# Microcontroller.net
KiCad netlist of a schematic drawn in Altium Designer
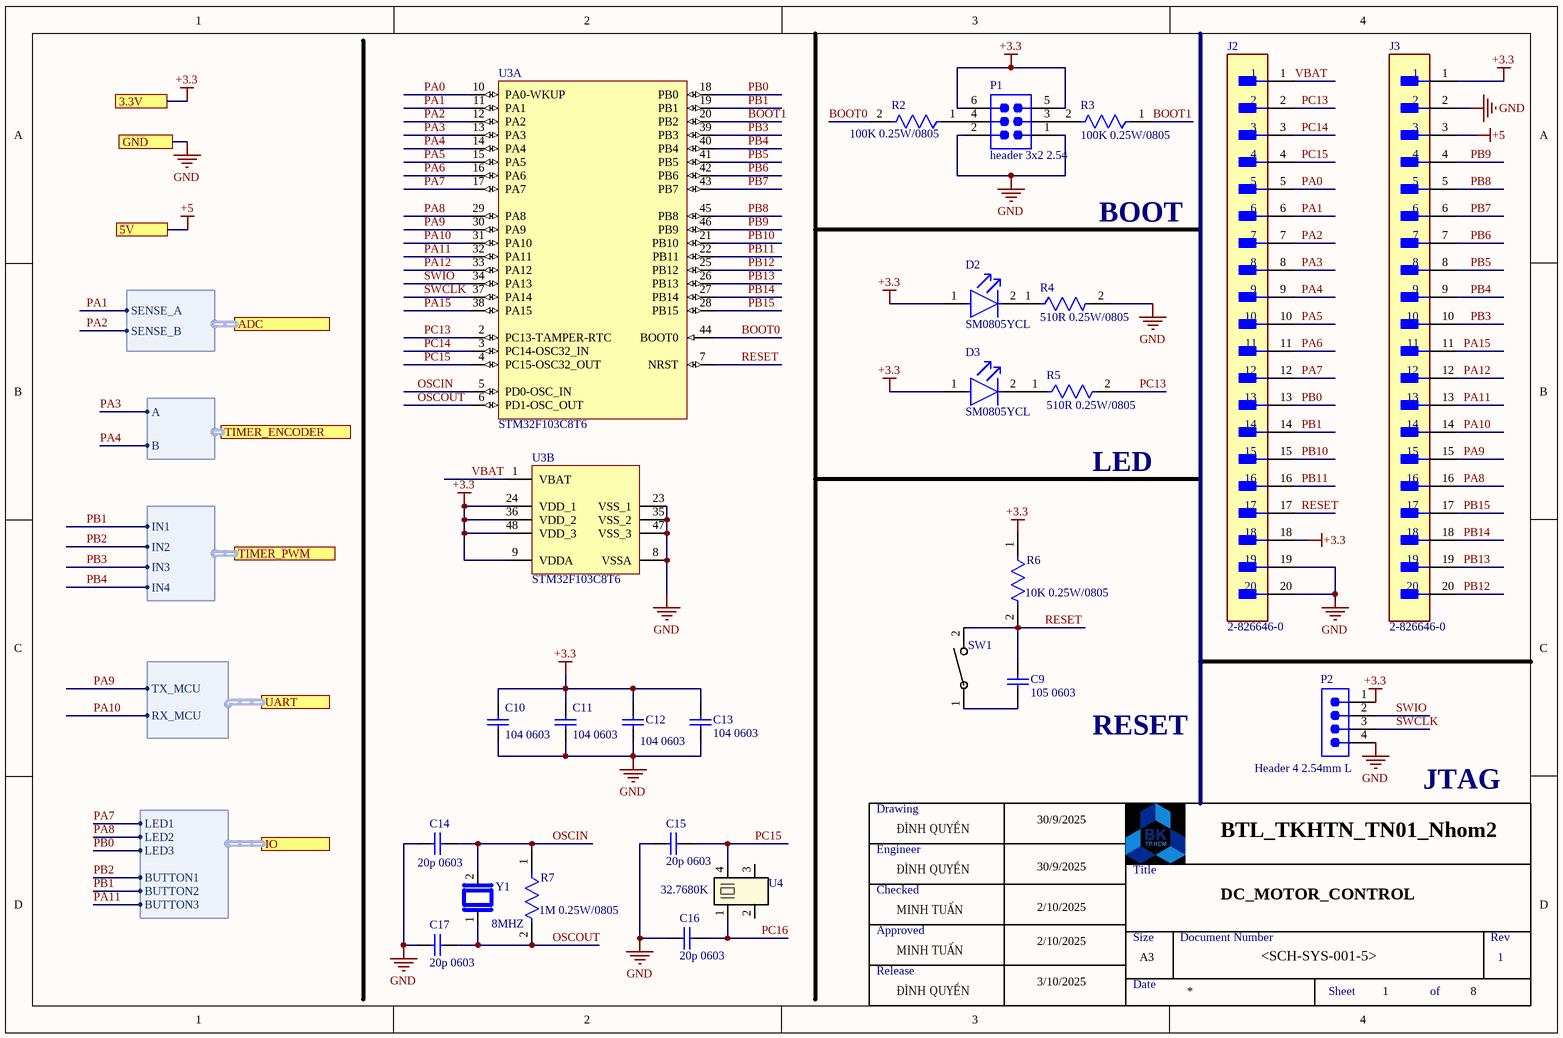
[diagram p0: Microcontroller.SchDoc]

(export (version "E")
  (design (tool "Eeschema 10.0.6"))
  (components
    (comp (ref "C9")
      (value "105 0603")
      (footprint "CAPC1608X92X38ML15T08")
      (fields (field (name "MANUFACTURER") "Vitramon") (field (name "PART NUMBER") "VJ0603Y103JXXAC"))
      (libsource (lib "Altium Content Vault") (part "CAP"))
    )
    (comp (ref "C10")
      (value "104 0603")
      (footprint "CAPC1608X92X38ML15T08")
      (fields (field (name "MANUFACTURER") "Vitramon") (field (name "PART NUMBER") "VJ0603Y103JXXAC"))
      (libsource (lib "Altium Content Vault") (part "CAP"))
    )
    (comp (ref "C11")
      (value "104 0603")
      (footprint "CAPC1608X92X38ML15T08")
      (fields (field (name "MANUFACTURER") "Vitramon") (field (name "PART NUMBER") "VJ0603Y103JXXAC"))
      (libsource (lib "Altium Content Vault") (part "CAP"))
    )
    (comp (ref "C12")
      (value "104 0603")
      (footprint "CAPC1608X92X38ML15T08")
      (fields (field (name "MANUFACTURER") "Vitramon") (field (name "PART NUMBER") "VJ0603Y103JXXAC"))
      (libsource (lib "Altium Content Vault") (part "CAP"))
    )
    (comp (ref "C13")
      (value "104 0603")
      (footprint "CAPC1608X92X38ML15T08")
      (fields (field (name "MANUFACTURER") "Vitramon") (field (name "PART NUMBER") "VJ0603Y103JXXAC"))
      (libsource (lib "Altium Content Vault") (part "CAP"))
    )
    (comp (ref "C14")
      (value "20p 0603")
      (footprint "CAPC1608X92X38ML15T08")
      (fields (field (name "MANUFACTURER") "Vitramon") (field (name "PART NUMBER") "VJ0603Y103JXXAC"))
      (libsource (lib "Altium Content Vault") (part "CAP"))
    )
    (comp (ref "C15")
      (value "20p 0603")
      (footprint "CAPC1608X92X38ML15T08")
      (fields (field (name "MANUFACTURER") "Vitramon") (field (name "PART NUMBER") "VJ0603Y103JXXAC"))
      (libsource (lib "Altium Content Vault") (part "CAP"))
    )
    (comp (ref "C16")
      (value "20p 0603")
      (footprint "CAPC1608X92X38ML15T08")
      (fields (field (name "MANUFACTURER") "Vitramon") (field (name "PART NUMBER") "VJ0603Y103JXXAC"))
      (libsource (lib "Altium Content Vault") (part "CAP"))
    )
    (comp (ref "C17")
      (value "20p 0603")
      (footprint "CAPC1608X92X38ML15T08")
      (fields (field (name "MANUFACTURER") "Vitramon") (field (name "PART NUMBER") "VJ0603Y103JXXAC"))
      (libsource (lib "Altium Content Vault") (part "CAP"))
    )
    (comp (ref "D2")
      (value "SM0805YCL")
      (footprint "FP-SM0805YCL-MFG")
      (description "LED YELLOW CLEAR 0805 SMD")
      (libsource (lib "Altium Content Vault") (part "ab1c01a81903e929fc6c44469aada92"))
    )
    (comp (ref "D3")
      (value "SM0805YCL")
      (footprint "FP-SM0805YCL-MFG")
      (description "LED YELLOW CLEAR 0805 SMD")
      (libsource (lib "Altium Content Vault") (part "ab1c01a81903e929fc6c44469aada92"))
    )
    (comp (ref "J2")
      (value "2-826646-0")
      (footprint "FP-2-826646-0-MFG")
      (description "CONN HEADER VERT 20POS 2.54MM")
      (libsource (lib "Altium Content Vault") (part "09d5f2461bb0697fba3bd732061644e"))
    )
    (comp (ref "J3")
      (value "2-826646-0")
      (footprint "FP-2-826646-0-MFG")
      (description "CONN HEADER VERT 20POS 2.54MM")
      (libsource (lib "Altium Content Vault") (part "09d5f2461bb0697fba3bd732061644e"))
    )
    (comp (ref "P1")
      (value "header 3x2 2.54")
      (footprint "SMTC-TSW-103-08-X-D")
      (description "0.025\" SQ Post Header, Through-hole, Vertical, -55 to 125 degC, 2.54 mm Pitch, 6-Pin, Male, RoHS")
      (fields (field (name "MANUFACTURER") "Samtec") (field (name "PARTNUMBER") "TSW-103-08-F-D"))
      (libsource (lib "Altium Content Vault") (part "SMTC-TSW-103-08-X-D"))
    )
    (comp (ref "P2")
      (value "Header 4 2.54mm L")
      (footprint "SMTC-TSW-104-08-X-S")
      (description "0.025\" SQ Post Header, Through-hole, Vertical, -55 to 125 degC, 2.54 mm Pitch, 4-Pin, Male, RoHS")
      (fields (field (name "MANUFACTURER") "Samtec") (field (name "PARTNUMBER") "TSW-104-08-G-S"))
      (libsource (lib "Altium Content Vault") (part "SMTC-TSW-104-08-X-S"))
    )
    (comp (ref "R2")
      (value "100K 0.25W/0805")
      (footprint "FP-AF0805-IPC_C")
      (description "Anti-Sulfurated Chip Resistor Automotive Grade 75Ω 1% 0.125W ±100ppm/°C 0805")
      (fields (field (name "TOLERANCE") "1%"))
      (libsource (lib "Altium Content Vault") (part "1029c3af85768c4190bb7ad29bc67b5"))
    )
    (comp (ref "R3")
      (value "100K 0.25W/0805")
      (footprint "FP-AF0805-IPC_C")
      (description "Anti-Sulfurated Chip Resistor Automotive Grade 75Ω 1% 0.125W ±100ppm/°C 0805")
      (fields (field (name "TOLERANCE") "1%"))
      (libsource (lib "Altium Content Vault") (part "1029c3af85768c4190bb7ad29bc67b5"))
    )
    (comp (ref "R4")
      (value "510R 0.25W/0805")
      (footprint "FP-AF0805-IPC_C")
      (description "Anti-Sulfurated Chip Resistor Automotive Grade 75Ω 1% 0.125W ±100ppm/°C 0805")
      (fields (field (name "TOLERANCE") "1%"))
      (libsource (lib "Altium Content Vault") (part "1029c3af85768c4190bb7ad29bc67b5"))
    )
    (comp (ref "R5")
      (value "510R 0.25W/0805")
      (footprint "FP-AF0805-IPC_C")
      (description "Anti-Sulfurated Chip Resistor Automotive Grade 75Ω 1% 0.125W ±100ppm/°C 0805")
      (fields (field (name "TOLERANCE") "1%"))
      (libsource (lib "Altium Content Vault") (part "1029c3af85768c4190bb7ad29bc67b5"))
    )
    (comp (ref "R6")
      (value "10K 0.25W/0805")
      (footprint "FP-AF0805-IPC_C")
      (description "Anti-Sulfurated Chip Resistor Automotive Grade 75Ω 1% 0.125W ±100ppm/°C 0805")
      (fields (field (name "TOLERANCE") "1%"))
      (libsource (lib "Altium Content Vault") (part "1029c3af85768c4190bb7ad29bc67b5"))
    )
    (comp (ref "R7")
      (value "1M 0.25W/0805")
      (footprint "FP-AF0805-IPC_C")
      (description "Anti-Sulfurated Chip Resistor Automotive Grade 75Ω 1% 0.125W ±100ppm/°C 0805")
      (fields (field (name "TOLERANCE") "1%"))
      (libsource (lib "Altium Content Vault") (part "1029c3af85768c4190bb7ad29bc67b5"))
    )
    (comp (ref "SW1")
      (value "PTS636 SM50J SMTR LFS")
      (footprint "SW_PTS636_CNK")
      (description "No Description Available")
      (fields (field (name "COPYRIGHT") "Copyright (C) 2025 Ultra Librarian. All rights reserved."))
      (libsource (lib "PTS636SM50JSMTRLFS") (part "PTS636 SM50J SMTR LFS"))
    )
    (comp (ref "U3")
      (value "STM32F103C8T6")
      (footprint "STM-LQFP48_L")
      (libsource (lib "Altium Content Vault") (part "MC-ARM-STM32F103X8_B-SQ48"))
    )
    (comp (ref "U4")
      (value "32.7680K")
      (footprint "SOJ_MC-306_EPS")
      (description "No Description Available")
      (fields
        (field (name "MANUFACTURER_PART_NUMBER") "MC-306 32.7680K-A3: ROHS")
        (field (name "COPYRIGHT") "Copyright (C) 2025 Ultra Librarian. All rights reserved.")
      )
      (libsource (lib "MC-30632P7680K-A3&colon_ROHS") (part "MC-306 32.7680K-A3{colon} ROHS"))
    )
    (comp (ref "Y1")
      (value "8MHZ")
      (footprint "XTAL_HC49P488W43L1150T466H350")
      (description "16 MHz Â±30ppm Crystal 18pF 50 Ohms HC-49/US")
      (fields (field (name "MF") "Citizen Finedevice") (field (name "MP") "HC-49/U-S16000000ABJB"))
      (libsource (lib "HC-49_U-S16000000ABJB") (part "HC-49/U-S16000000ABJB"))
    )
  )
  (nets
    (net (code "6") (name "+3.3") (class "Default")
      (node (ref "C10") (pin "2") (pinfunction "2_2") (pintype "passive"))
      (node (ref "C11") (pin "2") (pinfunction "2_2") (pintype "passive"))
      (node (ref "C12") (pin "2") (pinfunction "2_2") (pintype "passive"))
      (node (ref "C13") (pin "2") (pinfunction "2_2") (pintype "passive"))
      (node (ref "D2") (pin "1") (pinfunction "A_1") (pintype "passive"))
      (node (ref "D3") (pin "1") (pinfunction "A_1") (pintype "passive"))
      (node (ref "J2") (pin "18") (pinfunction "18_18") (pintype "passive"))
      (node (ref "J3") (pin "1") (pinfunction "1_1") (pintype "passive"))
      (node (ref "P1") (pin "5") (pinfunction "5_5") (pintype "passive"))
      (node (ref "P1") (pin "6") (pinfunction "6_6") (pintype "passive"))
      (node (ref "P2") (pin "1") (pinfunction "1_1") (pintype "passive"))
      (node (ref "R6") (pin "1") (pinfunction "1_1") (pintype "passive"))
      (node (ref "U3") (pin "24") (pinfunction "VDD_1_24") (pintype "power_in"))
      (node (ref "U3") (pin "36") (pinfunction "VDD_2_36") (pintype "power_in"))
      (node (ref "U3") (pin "48") (pinfunction "VDD_3_48") (pintype "power_in"))
      (node (ref "U3") (pin "9") (pinfunction "VDDA_9") (pintype "power_in"))
    )
    (net (code "7") (name "+5") (class "Default")
      (node (ref "J3") (pin "3") (pinfunction "3_3") (pintype "passive"))
    )
    (net (code "8") (name "/BOOT0") (class "Default")
      (node (ref "R2") (pin "2") (pinfunction "2_2") (pintype "passive"))
      (node (ref "U3") (pin "44") (pinfunction "BOOT0_44") (pintype "input"))
    )
    (net (code "9") (name "/BOOT1") (class "Default")
      (node (ref "R3") (pin "1") (pinfunction "1_1") (pintype "passive"))
      (node (ref "U3") (pin "20") (pinfunction "PB2_20") (pintype "bidirectional"))
    )
    (net (code "10") (name "/OSCIN") (class "Default")
      (node (ref "C14") (pin "1") (pinfunction "1_1") (pintype "passive"))
      (node (ref "R7") (pin "1") (pinfunction "1_1") (pintype "passive"))
      (node (ref "U3") (pin "5") (pinfunction "PD0-OSC_IN_5") (pintype "bidirectional"))
      (node (ref "Y1") (pin "2") (pinfunction "2_2") (pintype "passive"))
    )
    (net (code "11") (name "/OSCOUT") (class "Default")
      (node (ref "C17") (pin "1") (pinfunction "1_1") (pintype "passive"))
      (node (ref "R7") (pin "2") (pinfunction "2_2") (pintype "passive"))
      (node (ref "U3") (pin "6") (pinfunction "PD1-OSC_OUT_6") (pintype "bidirectional"))
      (node (ref "Y1") (pin "1") (pinfunction "1_1") (pintype "passive"))
    )
    (net (code "12") (name "/PA0") (class "Default")
      (node (ref "J2") (pin "5") (pinfunction "5_5") (pintype "passive"))
      (node (ref "U3") (pin "10") (pinfunction "PA0-WKUP_10") (pintype "bidirectional"))
    )
    (net (code "13") (name "/PA1") (class "Default")
      (node (ref "J2") (pin "6") (pinfunction "6_6") (pintype "passive"))
      (node (ref "U3") (pin "11") (pinfunction "PA1_11") (pintype "bidirectional"))
    )
    (net (code "14") (name "/PA2") (class "Default")
      (node (ref "J2") (pin "7") (pinfunction "7_7") (pintype "passive"))
      (node (ref "U3") (pin "12") (pinfunction "PA2_12") (pintype "bidirectional"))
    )
    (net (code "15") (name "/PA3") (class "Default")
      (node (ref "J2") (pin "8") (pinfunction "8_8") (pintype "passive"))
      (node (ref "U3") (pin "13") (pinfunction "PA3_13") (pintype "bidirectional"))
    )
    (net (code "16") (name "/PA4") (class "Default")
      (node (ref "J2") (pin "9") (pinfunction "9_9") (pintype "passive"))
      (node (ref "U3") (pin "14") (pinfunction "PA4_14") (pintype "bidirectional"))
    )
    (net (code "17") (name "/PA5") (class "Default")
      (node (ref "J2") (pin "10") (pinfunction "10_10") (pintype "passive"))
      (node (ref "U3") (pin "15") (pinfunction "PA5_15") (pintype "bidirectional"))
    )
    (net (code "18") (name "/PA6") (class "Default")
      (node (ref "J2") (pin "11") (pinfunction "11_11") (pintype "passive"))
      (node (ref "U3") (pin "16") (pinfunction "PA6_16") (pintype "bidirectional"))
    )
    (net (code "19") (name "/PA7") (class "Default")
      (node (ref "J2") (pin "12") (pinfunction "12_12") (pintype "passive"))
      (node (ref "U3") (pin "17") (pinfunction "PA7_17") (pintype "bidirectional"))
    )
    (net (code "20") (name "/PA8") (class "Default")
      (node (ref "J3") (pin "16") (pinfunction "16_16") (pintype "passive"))
      (node (ref "U3") (pin "29") (pinfunction "PA8_29") (pintype "bidirectional"))
    )
    (net (code "21") (name "/PA9") (class "Default")
      (node (ref "J3") (pin "15") (pinfunction "15_15") (pintype "passive"))
      (node (ref "U3") (pin "30") (pinfunction "PA9_30") (pintype "bidirectional"))
    )
    (net (code "22") (name "/PA10") (class "Default")
      (node (ref "J3") (pin "14") (pinfunction "14_14") (pintype "passive"))
      (node (ref "U3") (pin "31") (pinfunction "PA10_31") (pintype "bidirectional"))
    )
    (net (code "23") (name "/PA11") (class "Default")
      (node (ref "J3") (pin "13") (pinfunction "13_13") (pintype "passive"))
      (node (ref "U3") (pin "32") (pinfunction "PA11_32") (pintype "bidirectional"))
    )
    (net (code "24") (name "/PA12") (class "Default")
      (node (ref "J3") (pin "12") (pinfunction "12_12") (pintype "passive"))
      (node (ref "U3") (pin "33") (pinfunction "PA12_33") (pintype "bidirectional"))
    )
    (net (code "25") (name "/PA15") (class "Default")
      (node (ref "J3") (pin "11") (pinfunction "11_11") (pintype "passive"))
      (node (ref "U3") (pin "38") (pinfunction "PA15_38") (pintype "bidirectional"))
    )
    (net (code "26") (name "/PB0") (class "Default")
      (node (ref "J2") (pin "13") (pinfunction "13_13") (pintype "passive"))
      (node (ref "U3") (pin "18") (pinfunction "PB0_18") (pintype "bidirectional"))
    )
    (net (code "27") (name "/PB1") (class "Default")
      (node (ref "J2") (pin "14") (pinfunction "14_14") (pintype "passive"))
      (node (ref "U3") (pin "19") (pinfunction "PB1_19") (pintype "bidirectional"))
    )
    (net (code "29") (name "/PB3") (class "Default")
      (node (ref "J3") (pin "10") (pinfunction "10_10") (pintype "passive"))
      (node (ref "U3") (pin "39") (pinfunction "PB3_39") (pintype "bidirectional"))
    )
    (net (code "30") (name "/PB4") (class "Default")
      (node (ref "J3") (pin "9") (pinfunction "9_9") (pintype "passive"))
      (node (ref "U3") (pin "40") (pinfunction "PB4_40") (pintype "bidirectional"))
    )
    (net (code "31") (name "/PB5") (class "Default")
      (node (ref "J3") (pin "8") (pinfunction "8_8") (pintype "passive"))
      (node (ref "U3") (pin "41") (pinfunction "PB5_41") (pintype "bidirectional"))
    )
    (net (code "32") (name "/PB6") (class "Default")
      (node (ref "J3") (pin "7") (pinfunction "7_7") (pintype "passive"))
      (node (ref "U3") (pin "42") (pinfunction "PB6_42") (pintype "bidirectional"))
    )
    (net (code "33") (name "/PB7") (class "Default")
      (node (ref "J3") (pin "6") (pinfunction "6_6") (pintype "passive"))
      (node (ref "U3") (pin "43") (pinfunction "PB7_43") (pintype "bidirectional"))
    )
    (net (code "34") (name "/PB8") (class "Default")
      (node (ref "J3") (pin "5") (pinfunction "5_5") (pintype "passive"))
      (node (ref "U3") (pin "45") (pinfunction "PB8_45") (pintype "bidirectional"))
    )
    (net (code "35") (name "/PB9") (class "Default")
      (node (ref "J3") (pin "4") (pinfunction "4_4") (pintype "passive"))
      (node (ref "U3") (pin "46") (pinfunction "PB9_46") (pintype "bidirectional"))
    )
    (net (code "36") (name "/PB10") (class "Default")
      (node (ref "J2") (pin "15") (pinfunction "15_15") (pintype "passive"))
      (node (ref "U3") (pin "21") (pinfunction "PB10_21") (pintype "bidirectional"))
    )
    (net (code "37") (name "/PB11") (class "Default")
      (node (ref "J2") (pin "16") (pinfunction "16_16") (pintype "passive"))
      (node (ref "U3") (pin "22") (pinfunction "PB11_22") (pintype "bidirectional"))
    )
    (net (code "38") (name "/PB12") (class "Default")
      (node (ref "J3") (pin "20") (pinfunction "20_20") (pintype "passive"))
      (node (ref "U3") (pin "25") (pinfunction "PB12_25") (pintype "bidirectional"))
    )
    (net (code "39") (name "/PB13") (class "Default")
      (node (ref "J3") (pin "19") (pinfunction "19_19") (pintype "passive"))
      (node (ref "U3") (pin "26") (pinfunction "PB13_26") (pintype "bidirectional"))
    )
    (net (code "40") (name "/PB14") (class "Default")
      (node (ref "J3") (pin "18") (pinfunction "18_18") (pintype "passive"))
      (node (ref "U3") (pin "27") (pinfunction "PB14_27") (pintype "bidirectional"))
    )
    (net (code "41") (name "/PB15") (class "Default")
      (node (ref "J3") (pin "17") (pinfunction "17_17") (pintype "passive"))
      (node (ref "U3") (pin "28") (pinfunction "PB15_28") (pintype "bidirectional"))
    )
    (net (code "42") (name "/PC13") (class "Default")
      (node (ref "J2") (pin "2") (pinfunction "2_2") (pintype "passive"))
      (node (ref "R5") (pin "2") (pinfunction "2_2") (pintype "passive"))
      (node (ref "U3") (pin "2") (pinfunction "PC13-TAMPER-RTC_2") (pintype "bidirectional"))
    )
    (net (code "43") (name "/PC14") (class "Default")
      (node (ref "J2") (pin "3") (pinfunction "3_3") (pintype "passive"))
      (node (ref "U3") (pin "3") (pinfunction "PC14-OSC32_IN_3") (pintype "bidirectional"))
    )
    (net (code "44") (name "/PC15") (class "Default")
      (node (ref "C15") (pin "1") (pinfunction "1_1") (pintype "passive"))
      (node (ref "J2") (pin "4") (pinfunction "4_4") (pintype "passive"))
      (node (ref "U3") (pin "4") (pinfunction "PC15-OSC32_OUT_4") (pintype "bidirectional"))
      (node (ref "U4") (pin "4") (pinfunction "4_4") (pintype "passive"))
    )
    (net (code "45") (name "/PC16") (class "Default")
      (node (ref "C16") (pin "1") (pinfunction "1_1") (pintype "passive"))
      (node (ref "U4") (pin "1") (pinfunction "1_1") (pintype "passive"))
    )
    (net (code "46") (name "/RESET") (class "Default")
      (node (ref "C9") (pin "2") (pinfunction "2_2") (pintype "passive"))
      (node (ref "J2") (pin "17") (pinfunction "17_17") (pintype "passive"))
      (node (ref "R6") (pin "2") (pinfunction "2_2") (pintype "passive"))
      (node (ref "SW1") (pin "2") (pinfunction "2_2") (pintype "passive"))
      (node (ref "U3") (pin "7") (pinfunction "NRST_7") (pintype "bidirectional"))
    )
    (net (code "47") (name "/SWCLK") (class "Default")
      (node (ref "P2") (pin "3") (pinfunction "3_3") (pintype "passive"))
      (node (ref "U3") (pin "37") (pinfunction "PA14_37") (pintype "bidirectional"))
    )
    (net (code "48") (name "/SWIO") (class "Default")
      (node (ref "P2") (pin "2") (pinfunction "2_2") (pintype "passive"))
      (node (ref "U3") (pin "34") (pinfunction "PA13_34") (pintype "bidirectional"))
    )
    (net (code "49") (name "/VBAT") (class "Default")
      (node (ref "J2") (pin "1") (pinfunction "1_1") (pintype "passive"))
      (node (ref "U3") (pin "1") (pinfunction "VBAT_1") (pintype "power_in"))
    )
    (net (code "55") (name "GND") (class "Default")
      (node (ref "C10") (pin "1") (pinfunction "1_1") (pintype "passive"))
      (node (ref "C11") (pin "1") (pinfunction "1_1") (pintype "passive"))
      (node (ref "C12") (pin "1") (pinfunction "1_1") (pintype "passive"))
      (node (ref "C13") (pin "1") (pinfunction "1_1") (pintype "passive"))
      (node (ref "C14") (pin "2") (pinfunction "2_2") (pintype "passive"))
      (node (ref "C15") (pin "2") (pinfunction "2_2") (pintype "passive"))
      (node (ref "C16") (pin "2") (pinfunction "2_2") (pintype "passive"))
      (node (ref "C17") (pin "2") (pinfunction "2_2") (pintype "passive"))
      (node (ref "J2") (pin "19") (pinfunction "19_19") (pintype "passive"))
      (node (ref "J2") (pin "20") (pinfunction "20_20") (pintype "passive"))
      (node (ref "J3") (pin "2") (pinfunction "2_2") (pintype "passive"))
      (node (ref "P1") (pin "1") (pinfunction "1_1") (pintype "passive"))
      (node (ref "P1") (pin "2") (pinfunction "2_2") (pintype "passive"))
      (node (ref "P2") (pin "4") (pinfunction "4_4") (pintype "passive"))
      (node (ref "R4") (pin "2") (pinfunction "2_2") (pintype "passive"))
      (node (ref "U3") (pin "23") (pinfunction "VSS_1_23") (pintype "power_in"))
      (node (ref "U3") (pin "35") (pinfunction "VSS_2_35") (pintype "power_in"))
      (node (ref "U3") (pin "47") (pinfunction "VSS_3_47") (pintype "power_in"))
      (node (ref "U3") (pin "8") (pinfunction "VSSA_8") (pintype "power_in"))
    )
    (net (code "56") (name "Net-(C9-Pad1)") (class "Default")
      (node (ref "C9") (pin "1") (pinfunction "1_1") (pintype "passive"))
      (node (ref "SW1") (pin "1") (pinfunction "1_1") (pintype "passive"))
    )
    (net (code "57") (name "Net-(D3-C)") (class "Default")
      (node (ref "D3") (pin "2") (pinfunction "C_2") (pintype "passive"))
      (node (ref "R5") (pin "1") (pinfunction "1_1") (pintype "passive"))
    )
    (net (code "58") (name "Net-(P1-Pad3)") (class "Default")
      (node (ref "P1") (pin "3") (pinfunction "3_3") (pintype "passive"))
      (node (ref "R3") (pin "2") (pinfunction "2_2") (pintype "passive"))
    )
    (net (code "59") (name "Net-(P1-Pad4)") (class "Default")
      (node (ref "P1") (pin "4") (pinfunction "4_4") (pintype "passive"))
      (node (ref "R2") (pin "1") (pinfunction "1_1") (pintype "passive"))
    )
    (net (code "60") (name "unconnected-(D2-C-Pad2)") (class "Default")
      (node (ref "D2") (pin "2") (pinfunction "C_2") (pintype "passive"))
    )
    (net (code "61") (name "unconnected-(R4-Pad1)") (class "Default")
      (node (ref "R4") (pin "1") (pinfunction "1_1") (pintype "passive"))
    )
    (net (code "62") (name "unconnected-(U4-Pad2)") (class "Default")
      (node (ref "U4") (pin "2") (pinfunction "2_2") (pintype "passive"))
    )
    (net (code "63") (name "unconnected-(U4-Pad3)") (class "Default")
      (node (ref "U4") (pin "3") (pinfunction "3_3") (pintype "passive"))
    )
  )
)
